# I2C_ISO.net
KiCad netlist of a schematic drawn in Altium Designer
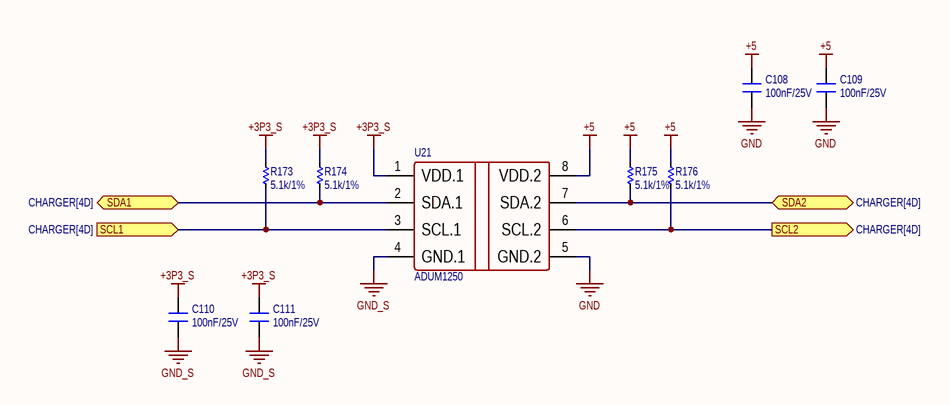
[diagram p0: I2C_ISO.SchDoc]

(export (version "E")
  (design (tool "Eeschema 10.0.6"))
  (components
    (comp (ref "C108")
      (value "100nF/25V")
      (footprint "CN-SMD-0603")
      (description "CL10B104KA8NNNC")
      (libsource (lib "Library") (part "CN"))
    )
    (comp (ref "C109")
      (value "100nF/25V")
      (footprint "CN-SMD-0603")
      (description "CL10B104KA8NNNC")
      (libsource (lib "Library") (part "CN"))
    )
    (comp (ref "C110")
      (value "100nF/25V")
      (footprint "CN-SMD-0603")
      (description "CL10B104KA8NNNC")
      (libsource (lib "Library") (part "CN"))
    )
    (comp (ref "C111")
      (value "100nF/25V")
      (footprint "CN-SMD-0603")
      (description "CL10B104KA8NNNC")
      (libsource (lib "Library") (part "CN"))
    )
    (comp (ref "R173")
      (value "5.1k/1%")
      (footprint "RES-SMD-0603")
      (description "ERJ-3EKF5101V")
      (fields
        (field (name "MANUFACTURER") "Generic Components")
        (field (name "PUBLISHER") "Altium Hobart Technology Centre")
      )
      (libsource (lib "Library") (part "Res-SMD"))
    )
    (comp (ref "R174")
      (value "5.1k/1%")
      (footprint "RES-SMD-0603")
      (description "ERJ-3EKF5101V")
      (fields
        (field (name "MANUFACTURER") "Generic Components")
        (field (name "PUBLISHER") "Altium Hobart Technology Centre")
      )
      (libsource (lib "Library") (part "Res-SMD"))
    )
    (comp (ref "R175")
      (value "5.1k/1%")
      (footprint "RES-SMD-0603")
      (description "ERJ-3EKF5101V")
      (fields
        (field (name "MANUFACTURER") "Generic Components")
        (field (name "PUBLISHER") "Altium Hobart Technology Centre")
      )
      (libsource (lib "Library") (part "Res-SMD"))
    )
    (comp (ref "R176")
      (value "5.1k/1%")
      (footprint "RES-SMD-0603")
      (description "ERJ-3EKF5101V")
      (fields
        (field (name "MANUFACTURER") "Generic Components")
        (field (name "PUBLISHER") "Altium Hobart Technology Centre")
      )
      (libsource (lib "Library") (part "Res-SMD"))
    )
    (comp (ref "U21")
      (value "ADUM1250")
      (footprint "SO8")
      (description "Hot Swappable, Dual I2C Isolators")
      (libsource (lib "Library") (part "ADUM1250"))
    )
  )
  (nets
    (net (code "1") (name "+3P3_S") (class "Default")
      (node (ref "C110") (pin "1") (pinfunction "1_1") (pintype "passive"))
      (node (ref "C111") (pin "1") (pinfunction "1_1") (pintype "passive"))
      (node (ref "R173") (pin "1") (pinfunction "1_1") (pintype "passive"))
      (node (ref "R174") (pin "1") (pinfunction "1_1") (pintype "passive"))
      (node (ref "U21") (pin "1") (pinfunction "VDD.1_1") (pintype "passive"))
    )
    (net (code "2") (name "+5") (class "Default")
      (node (ref "C108") (pin "1") (pinfunction "1_1") (pintype "passive"))
      (node (ref "C109") (pin "1") (pinfunction "1_1") (pintype "passive"))
      (node (ref "R175") (pin "1") (pinfunction "1_1") (pintype "passive"))
      (node (ref "R176") (pin "1") (pinfunction "1_1") (pintype "passive"))
      (node (ref "U21") (pin "8") (pinfunction "VDD.2_8") (pintype "passive"))
    )
    (net (code "3") (name "/SCL1") (class "Default")
      (node (ref "R173") (pin "2") (pinfunction "2_2") (pintype "passive"))
      (node (ref "U21") (pin "3") (pinfunction "SCL.1_3") (pintype "passive"))
    )
    (net (code "4") (name "/SCL2") (class "Default")
      (node (ref "R176") (pin "2") (pinfunction "2_2") (pintype "passive"))
      (node (ref "U21") (pin "6") (pinfunction "SCL.2_6") (pintype "passive"))
    )
    (net (code "5") (name "/SDA1") (class "Default")
      (node (ref "R174") (pin "2") (pinfunction "2_2") (pintype "passive"))
      (node (ref "U21") (pin "2") (pinfunction "SDA.1_2") (pintype "passive"))
    )
    (net (code "6") (name "/SDA2") (class "Default")
      (node (ref "R175") (pin "2") (pinfunction "2_2") (pintype "passive"))
      (node (ref "U21") (pin "7") (pinfunction "SDA.2_7") (pintype "passive"))
    )
    (net (code "7") (name "GND") (class "Default")
      (node (ref "C108") (pin "2") (pinfunction "2_2") (pintype "passive"))
      (node (ref "C109") (pin "2") (pinfunction "2_2") (pintype "passive"))
      (node (ref "U21") (pin "5") (pinfunction "GND.2_5") (pintype "passive"))
    )
    (net (code "8") (name "GND_S") (class "Default")
      (node (ref "C110") (pin "2") (pinfunction "2_2") (pintype "passive"))
      (node (ref "C111") (pin "2") (pinfunction "2_2") (pintype "passive"))
      (node (ref "U21") (pin "4") (pinfunction "GND.1_4") (pintype "passive"))
    )
  )
)
